# design.net
KiCad netlist of a schematic drawn in Altium Designer
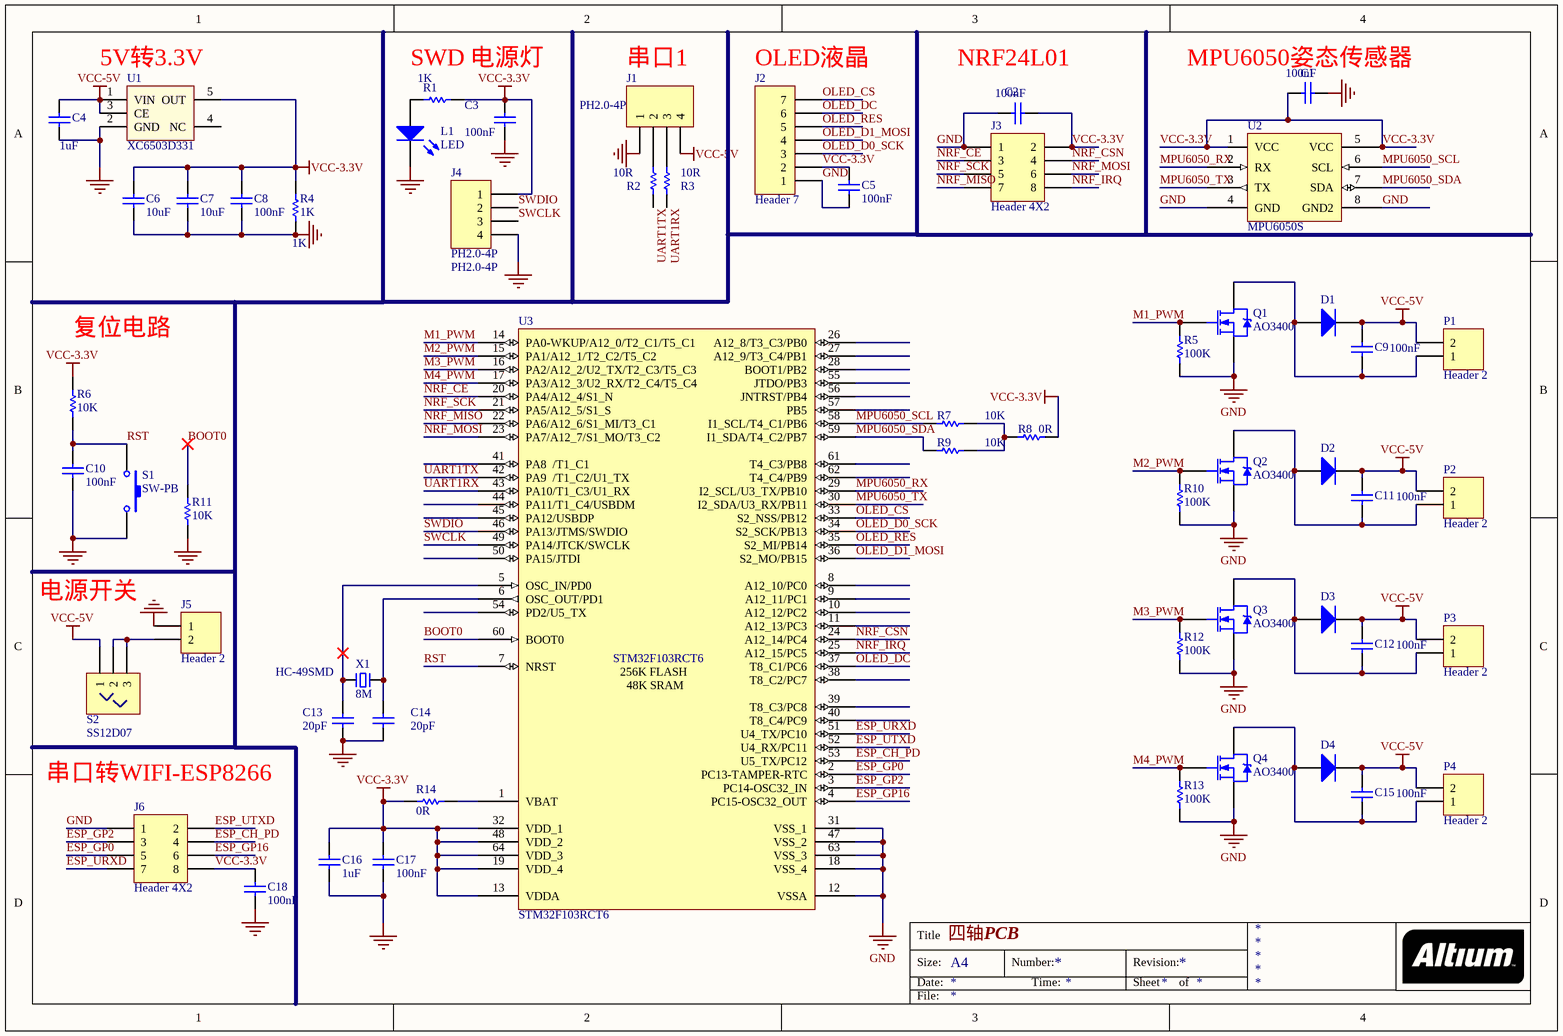
[diagram p0: 四轴.SchDoc]

(export (version "E")
  (design (tool "Eeschema 10.0.6"))
  (components
    (comp (ref "C1")
      (value "100nF")
      (footprint "LiyaoPCB库:0603")
      (description "Capacitor")
      (fields (field (name "PUBLISHER") "Altium Limited"))
      (libsource (lib "Miscellaneous Devices") (part "Cap"))
    )
    (comp (ref "C2")
      (value "100nF")
      (footprint "LiyaoPCB库:0603")
      (description "Capacitor")
      (fields (field (name "PUBLISHER") "Altium Limited"))
      (libsource (lib "Miscellaneous Devices") (part "Cap"))
    )
    (comp (ref "C3")
      (value "100nF")
      (footprint "0603")
      (description "Capacitor")
      (fields (field (name "PUBLISHER") "Altium Limited"))
      (libsource (lib "Miscellaneous Devices") (part "Cap"))
    )
    (comp (ref "C4")
      (value "1uF")
      (footprint "0603")
      (description "Capacitor")
      (fields (field (name "PUBLISHER") "Altium Limited"))
      (libsource (lib "Miscellaneous Devices") (part "Cap"))
    )
    (comp (ref "C5")
      (value "100nF")
      (footprint "LiyaoPCB库:0603")
      (description "Capacitor")
      (fields (field (name "PUBLISHER") "Altium Limited"))
      (libsource (lib "Miscellaneous Devices") (part "Cap"))
    )
    (comp (ref "C6")
      (value "10uF")
      (footprint "0603")
      (description "Capacitor")
      (fields (field (name "PUBLISHER") "Altium Limited"))
      (libsource (lib "Miscellaneous Devices") (part "Cap"))
    )
    (comp (ref "C7")
      (value "10uF")
      (footprint "0603")
      (description "Capacitor")
      (fields (field (name "PUBLISHER") "Altium Limited"))
      (libsource (lib "Miscellaneous Devices") (part "Cap"))
    )
    (comp (ref "C8")
      (value "100nF")
      (footprint "0603")
      (description "Capacitor")
      (fields (field (name "PUBLISHER") "Altium Limited"))
      (libsource (lib "Miscellaneous Devices") (part "Cap"))
    )
    (comp (ref "C9")
      (value "100nF")
      (footprint "0603")
      (description "Capacitor")
      (fields (field (name "PUBLISHER") "Altium Limited"))
      (libsource (lib "Miscellaneous Devices") (part "Cap"))
    )
    (comp (ref "C10")
      (value "100nF")
      (footprint "0603")
      (description "Capacitor")
      (fields (field (name "PUBLISHER") "Altium Limited"))
      (libsource (lib "Miscellaneous Devices") (part "Cap"))
    )
    (comp (ref "C11")
      (value "100nF")
      (footprint "0603")
      (description "Capacitor")
      (fields (field (name "PUBLISHER") "Altium Limited"))
      (libsource (lib "Miscellaneous Devices") (part "Cap"))
    )
    (comp (ref "C12")
      (value "100nF")
      (footprint "0603")
      (description "Capacitor")
      (fields (field (name "PUBLISHER") "Altium Limited"))
      (libsource (lib "Miscellaneous Devices") (part "Cap"))
    )
    (comp (ref "C13")
      (value "20pF")
      (footprint "0603")
      (description "Capacitor")
      (fields (field (name "PUBLISHER") "Altium Limited"))
      (libsource (lib "Miscellaneous Devices") (part "Cap"))
    )
    (comp (ref "C14")
      (value "20pF")
      (footprint "0603")
      (description "Capacitor")
      (fields (field (name "PUBLISHER") "Altium Limited"))
      (libsource (lib "Miscellaneous Devices") (part "Cap"))
    )
    (comp (ref "C15")
      (value "100nF")
      (footprint "0603")
      (description "Capacitor")
      (fields (field (name "PUBLISHER") "Altium Limited"))
      (libsource (lib "Miscellaneous Devices") (part "Cap"))
    )
    (comp (ref "C16")
      (value "1uF")
      (footprint "LiyaoPCB库:0603")
      (description "Capacitor")
      (fields (field (name "PUBLISHER") "Altium Limited"))
      (libsource (lib "Miscellaneous Devices") (part "Cap"))
    )
    (comp (ref "C17")
      (value "100nF")
      (footprint "LiyaoPCB库:0603")
      (description "Capacitor")
      (fields (field (name "PUBLISHER") "Altium Limited"))
      (libsource (lib "Miscellaneous Devices") (part "Cap"))
    )
    (comp (ref "C18")
      (value "100nF")
      (footprint "LiyaoPCB库:0603")
      (description "Capacitor")
      (fields (field (name "PUBLISHER") "Altium Limited"))
      (libsource (lib "Miscellaneous Devices") (part "Cap"))
    )
    (comp (ref "D1")
      (value "SS14")
      (footprint "LiyaoPCB库:SMA")
      (description "28V 1A")
      (fields (field (name "PUBLISHER") "Altium Limited"))
      (libsource (lib "Liyao原理图库") (part "SS14"))
    )
    (comp (ref "D2")
      (value "SS14")
      (footprint "LiyaoPCB库:SMA")
      (description "28V 1A")
      (fields (field (name "PUBLISHER") "Altium Limited"))
      (libsource (lib "Liyao原理图库") (part "SS14"))
    )
    (comp (ref "D3")
      (value "SS14")
      (footprint "LiyaoPCB库:SMA")
      (description "28V 1A")
      (fields (field (name "PUBLISHER") "Altium Limited"))
      (libsource (lib "Liyao原理图库") (part "SS14"))
    )
    (comp (ref "D4")
      (value "SS14")
      (footprint "LiyaoPCB库:SMA")
      (description "28V 1A")
      (fields (field (name "PUBLISHER") "Altium Limited"))
      (libsource (lib "Liyao原理图库") (part "SS14"))
    )
    (comp (ref "J1")
      (value "PH2.0-4P")
      (footprint "PH2.0-4P")
      (description "Header, 4-Pin")
      (fields (field (name "PUBLISHER") "Altium Limited"))
      (libsource (lib "Miscellaneous Connectors") (part "Header 4"))
    )
    (comp (ref "J2")
      (value "Header 7")
      (footprint "HDR1X7")
      (description "Header, 7-Pin")
      (fields (field (name "PUBLISHER") "Altium Limited"))
      (libsource (lib "Miscellaneous Connectors") (part "Header 7"))
    )
    (comp (ref "J3")
      (value "Header 4X2")
      (footprint "HDR2X4")
      (description "Header, 4-Pin, Dual row")
      (fields (field (name "PUBLISHER") "Altium Limited"))
      (libsource (lib "Miscellaneous Connectors") (part "Header 4X2"))
    )
    (comp (ref "J4")
      (value "PH2.0-4P")
      (footprint "PH2.0-4P")
      (description "Header, 4-Pin")
      (fields (field (name "ALTIUM_VALUE") "PH2.0-4P") (field (name "PUBLISHER") "Altium Limited"))
      (libsource (lib "") (part "Header 4_1"))
    )
    (comp (ref "J5")
      (value "Header 2")
      (footprint "PH2.0-2P")
      (description "Header, 2-Pin")
      (fields (field (name "PUBLISHER") "Altium Limited"))
      (libsource (lib "") (part "Header 2_1"))
    )
    (comp (ref "J6")
      (value "Header 4X2")
      (footprint "HDR2X4")
      (description "Header, 4-Pin, Dual row")
      (fields (field (name "PUBLISHER") "Altium Limited"))
      (libsource (lib "Miscellaneous Connectors") (part "Header 4X2"))
    )
    (comp (ref "L1") (value "LED") (footprint "0603") (libsource (lib "Sparks") (part "LED")))
    (comp (ref "P1")
      (value "Header 2")
      (footprint "HDR1X2")
      (description "Header, 2-Pin")
      (fields (field (name "PUBLISHER") "Altium Limited"))
      (libsource (lib "Miscellaneous Connectors") (part "Header 2"))
    )
    (comp (ref "P2")
      (value "Header 2")
      (footprint "HDR1X2")
      (description "Header, 2-Pin")
      (fields (field (name "PUBLISHER") "Altium Limited"))
      (libsource (lib "Miscellaneous Connectors") (part "Header 2"))
    )
    (comp (ref "P3")
      (value "Header 2")
      (footprint "HDR1X2")
      (description "Header, 2-Pin")
      (fields (field (name "PUBLISHER") "Altium Limited"))
      (libsource (lib "Miscellaneous Connectors") (part "Header 2"))
    )
    (comp (ref "P4")
      (value "Header 2")
      (footprint "HDR1X2")
      (description "Header, 2-Pin")
      (fields (field (name "PUBLISHER") "Altium Limited"))
      (libsource (lib "Miscellaneous Connectors") (part "Header 2"))
    )
    (comp (ref "Q1")
      (value "AO3400")
      (footprint "SOT-23")
      (description "N-Channel MOSFET")
      (fields (field (name "PUBLISHER") "Altium Limited"))
      (libsource (lib "Liyao原理图库") (part "MOS-N"))
    )
    (comp (ref "Q2")
      (value "AO3400")
      (footprint "SOT-23")
      (description "N-Channel MOSFET")
      (fields (field (name "PUBLISHER") "Altium Limited"))
      (libsource (lib "Liyao原理图库") (part "MOS-N"))
    )
    (comp (ref "Q3")
      (value "AO3400")
      (footprint "SOT-23")
      (description "N-Channel MOSFET")
      (fields (field (name "PUBLISHER") "Altium Limited"))
      (libsource (lib "Liyao原理图库") (part "MOS-N"))
    )
    (comp (ref "Q4")
      (value "AO3400")
      (footprint "SOT-23")
      (description "N-Channel MOSFET")
      (fields (field (name "PUBLISHER") "Altium Limited"))
      (libsource (lib "Liyao原理图库") (part "MOS-N"))
    )
    (comp (ref "R1")
      (value "1K")
      (footprint "0603")
      (description "Resistor")
      (fields (field (name "PUBLISHER") "Altium Limited"))
      (libsource (lib "Miscellaneous Devices") (part "Res1"))
    )
    (comp (ref "R2")
      (value "10R")
      (footprint "0603")
      (description "Resistor")
      (fields (field (name "PUBLISHER") "Altium Limited"))
      (libsource (lib "Miscellaneous Devices") (part "Res1"))
    )
    (comp (ref "R3")
      (value "10R")
      (footprint "0603")
      (description "Resistor")
      (fields (field (name "PUBLISHER") "Altium Limited"))
      (libsource (lib "Miscellaneous Devices") (part "Res1"))
    )
    (comp (ref "R4")
      (value "1K")
      (footprint "0603")
      (description "Resistor")
      (fields (field (name "ALTIUM_VALUE") "1K") (field (name "PUBLISHER") "Altium Limited"))
      (libsource (lib "Miscellaneous Devices") (part "Res1"))
    )
    (comp (ref "R5")
      (value "100K")
      (footprint "LiyaoPCB库:0603")
      (description "Resistor")
      (fields (field (name "PUBLISHER") "Altium Limited"))
      (libsource (lib "Miscellaneous Devices") (part "Res1"))
    )
    (comp (ref "R6")
      (value "10K")
      (footprint "0603")
      (description "Resistor")
      (fields (field (name "PUBLISHER") "Altium Limited"))
      (libsource (lib "Miscellaneous Devices") (part "Res1"))
    )
    (comp (ref "R7")
      (value "10K")
      (footprint "0603")
      (description "Resistor")
      (fields (field (name "PUBLISHER") "Altium Limited"))
      (libsource (lib "Miscellaneous Devices") (part "Res1"))
    )
    (comp (ref "R8")
      (value "0R")
      (footprint "0603")
      (description "Resistor")
      (fields (field (name "PUBLISHER") "Altium Limited"))
      (libsource (lib "Miscellaneous Devices") (part "Res1"))
    )
    (comp (ref "R9")
      (value "10K")
      (footprint "0603")
      (description "Resistor")
      (fields (field (name "PUBLISHER") "Altium Limited"))
      (libsource (lib "Miscellaneous Devices") (part "Res1"))
    )
    (comp (ref "R10")
      (value "100K")
      (footprint "LiyaoPCB库:0603")
      (description "Resistor")
      (fields (field (name "PUBLISHER") "Altium Limited"))
      (libsource (lib "Miscellaneous Devices") (part "Res1"))
    )
    (comp (ref "R11")
      (value "10K")
      (footprint "0603")
      (description "Resistor")
      (fields (field (name "PUBLISHER") "Altium Limited"))
      (libsource (lib "Miscellaneous Devices") (part "Res1"))
    )
    (comp (ref "R12")
      (value "100K")
      (footprint "LiyaoPCB库:0603")
      (description "Resistor")
      (fields (field (name "PUBLISHER") "Altium Limited"))
      (libsource (lib "Miscellaneous Devices") (part "Res1"))
    )
    (comp (ref "R13")
      (value "100K")
      (footprint "LiyaoPCB库:0603")
      (description "Resistor")
      (fields (field (name "PUBLISHER") "Altium Limited"))
      (libsource (lib "Miscellaneous Devices") (part "Res1"))
    )
    (comp (ref "R14")
      (value "0R")
      (footprint "0603")
      (description "Resistor")
      (fields (field (name "PUBLISHER") "Altium Limited"))
      (libsource (lib "Miscellaneous Devices") (part "Res1"))
    )
    (comp (ref "S1")
      (value "SW-PB")
      (footprint "SW-KEY")
      (description "Switch")
      (fields (field (name "PUBLISHER") "Altium Limited"))
      (libsource (lib "Miscellaneous Devices") (part "SW-PB"))
    )
    (comp (ref "S2")
      (value "SS12D07")
      (footprint "LiyaoPCB库:SS-12D07")
      (libsource (lib "Liyao原理图库") (part "SS12D07"))
    )
    (comp (ref "U1")
      (value "XC6503D331")
      (footprint "SOT23-5")
      (libsource (lib "CYSchlib") (part "XC6503Dxxx"))
    )
    (comp (ref "U2")
      (value "MPU6050S")
      (footprint "LiyaoPCB库:MPU6050S")
      (libsource (lib "Liyao原理图库") (part "MPU6050S"))
    )
    (comp (ref "U3")
      (value "STM32F103RCT6")
      (footprint "LQFP64_N")
      (description "256K Flash 48K RAM")
      (fields (field (name "PUBLISHER") "Altium Limited"))
      (libsource (lib "Liyao原理图库") (part "STM32F103RCT6"))
    )
    (comp (ref "X1")
      (value "8M")
      (footprint "HC-49SMD")
      (fields (field (name "ALTIUM_VALUE") "HC-49SMD"))
      (libsource (lib "CYSchlib") (part "XTAL"))
    )
  )
  (nets
    (net (code "1") (name "/BOOT0") (class "Default")
      (node (ref "R11") (pin "1") (pinfunction "1_1") (pintype "passive"))
      (node (ref "U3") (pin "60") (pinfunction "BOOT0_60") (pintype "input"))
    )
    (net (code "2") (name "/ESP_CH_PD") (class "Default")
      (node (ref "J6") (pin "4") (pinfunction "4_4") (pintype "passive"))
      (node (ref "U3") (pin "53") (pinfunction "U5_TX/PC12_53") (pintype "bidirectional"))
    )
    (net (code "3") (name "/ESP_GP0") (class "Default")
      (node (ref "J6") (pin "5") (pinfunction "5_5") (pintype "passive"))
      (node (ref "U3") (pin "2") (pinfunction "PC13-TAMPER-RTC_2") (pintype "bidirectional"))
    )
    (net (code "4") (name "/ESP_GP2") (class "Default")
      (node (ref "J6") (pin "3") (pinfunction "3_3") (pintype "passive"))
      (node (ref "U3") (pin "3") (pinfunction "PC14-OSC32_IN_3") (pintype "bidirectional"))
    )
    (net (code "5") (name "/ESP_GP16") (class "Default")
      (node (ref "J6") (pin "6") (pinfunction "6_6") (pintype "passive"))
      (node (ref "U3") (pin "4") (pinfunction "PC15-OSC32_OUT_4") (pintype "bidirectional"))
    )
    (net (code "6") (name "/ESP_URXD") (class "Default")
      (node (ref "J6") (pin "7") (pinfunction "7_7") (pintype "passive"))
      (node (ref "U3") (pin "51") (pinfunction "U4_TX/PC10_51") (pintype "bidirectional"))
    )
    (net (code "7") (name "/ESP_UTXD") (class "Default")
      (node (ref "J6") (pin "2") (pinfunction "2_2") (pintype "passive"))
      (node (ref "U3") (pin "52") (pinfunction "U4_RX/PC11_52") (pintype "bidirectional"))
    )
    (net (code "8") (name "/M1_PWM") (class "Default")
      (node (ref "Q1") (pin "1") (pinfunction "G_1") (pintype "passive"))
      (node (ref "R5") (pin "2") (pinfunction "2_2") (pintype "passive"))
      (node (ref "U3") (pin "14") (pinfunction "PA0-WKUP/A12_0/T2_C1/T5_C1_14") (pintype "bidirectional"))
    )
    (net (code "9") (name "/M2_PWM") (class "Default")
      (node (ref "Q2") (pin "1") (pinfunction "G_1") (pintype "passive"))
      (node (ref "R10") (pin "2") (pinfunction "2_2") (pintype "passive"))
      (node (ref "U3") (pin "15") (pinfunction "PA1/A12_1/T2_C2/T5_C2_15") (pintype "bidirectional"))
    )
    (net (code "10") (name "/M3_PWM") (class "Default")
      (node (ref "Q3") (pin "1") (pinfunction "G_1") (pintype "passive"))
      (node (ref "R12") (pin "2") (pinfunction "2_2") (pintype "passive"))
      (node (ref "U3") (pin "16") (pinfunction "PA2/A12_2/U2_TX/T2_C3/T5_C3_16") (pintype "bidirectional"))
    )
    (net (code "11") (name "/M4_PWM") (class "Default")
      (node (ref "Q4") (pin "1") (pinfunction "G_1") (pintype "passive"))
      (node (ref "R13") (pin "2") (pinfunction "2_2") (pintype "passive"))
      (node (ref "U3") (pin "17") (pinfunction "PA3/A12_3/U2_RX/T2_C4/T5_C4_17") (pintype "bidirectional"))
    )
    (net (code "12") (name "/MPU6050_RX") (class "Default")
      (node (ref "U2") (pin "2") (pinfunction "RX_2") (pintype "input"))
      (node (ref "U3") (pin "29") (pinfunction "I2_SCL/U3_TX/PB10_29") (pintype "bidirectional"))
    )
    (net (code "13") (name "/MPU6050_SCL") (class "Default")
      (node (ref "R7") (pin "1") (pinfunction "1_1") (pintype "passive"))
      (node (ref "U2") (pin "6") (pinfunction "SCL_6") (pintype "input"))
      (node (ref "U3") (pin "58") (pinfunction "I1_SCL/T4_C1/PB6_58") (pintype "bidirectional"))
    )
    (net (code "14") (name "/MPU6050_SDA") (class "Default")
      (node (ref "R9") (pin "1") (pinfunction "1_1") (pintype "passive"))
      (node (ref "U2") (pin "7") (pinfunction "SDA_7") (pintype "bidirectional"))
      (node (ref "U3") (pin "59") (pinfunction "I1_SDA/T4_C2/PB7_59") (pintype "bidirectional"))
    )
    (net (code "15") (name "/MPU6050_TX") (class "Default")
      (node (ref "U2") (pin "3") (pinfunction "TX_3") (pintype "output"))
      (node (ref "U3") (pin "30") (pinfunction "I2_SDA/U3_RX/PB11_30") (pintype "bidirectional"))
    )
    (net (code "16") (name "/NRF_CE") (class "Default")
      (node (ref "J3") (pin "3") (pinfunction "3_3") (pintype "passive"))
      (node (ref "U3") (pin "20") (pinfunction "PA4/A12_4/S1_N_20") (pintype "bidirectional"))
    )
    (net (code "17") (name "/NRF_CSN") (class "Default")
      (node (ref "J3") (pin "4") (pinfunction "4_4") (pintype "passive"))
      (node (ref "U3") (pin "24") (pinfunction "A12_14/PC4_24") (pintype "bidirectional"))
    )
    (net (code "18") (name "/NRF_IRQ") (class "Default")
      (node (ref "J3") (pin "8") (pinfunction "8_8") (pintype "passive"))
      (node (ref "U3") (pin "25") (pinfunction "A12_15/PC5_25") (pintype "bidirectional"))
    )
    (net (code "19") (name "/NRF_MISO") (class "Default")
      (node (ref "J3") (pin "7") (pinfunction "7_7") (pintype "passive"))
      (node (ref "U3") (pin "22") (pinfunction "PA6/A12_6/S1_MI/T3_C1_22") (pintype "bidirectional"))
    )
    (net (code "20") (name "/NRF_MOSI") (class "Default")
      (node (ref "J3") (pin "6") (pinfunction "6_6") (pintype "passive"))
      (node (ref "U3") (pin "23") (pinfunction "PA7/A12_7/S1_MO/T3_C2_23") (pintype "bidirectional"))
    )
    (net (code "21") (name "/NRF_SCK") (class "Default")
      (node (ref "J3") (pin "5") (pinfunction "5_5") (pintype "passive"))
      (node (ref "U3") (pin "21") (pinfunction "PA5/A12_5/S1_S_21") (pintype "bidirectional"))
    )
    (net (code "22") (name "/OLED_CS") (class "Default")
      (node (ref "J2") (pin "7") (pinfunction "7_7") (pintype "passive"))
      (node (ref "U3") (pin "33") (pinfunction "S2_NSS/PB12_33") (pintype "bidirectional"))
    )
    (net (code "23") (name "/OLED_D0_SCK") (class "Default")
      (node (ref "J2") (pin "3") (pinfunction "3_3") (pintype "passive"))
      (node (ref "U3") (pin "34") (pinfunction "S2_SCK/PB13_34") (pintype "bidirectional"))
    )
    (net (code "24") (name "/OLED_D1_MOSI") (class "Default")
      (node (ref "J2") (pin "4") (pinfunction "4_4") (pintype "passive"))
      (node (ref "U3") (pin "36") (pinfunction "S2_MO/PB15_36") (pintype "bidirectional"))
    )
    (net (code "25") (name "/OLED_DC") (class "Default")
      (node (ref "J2") (pin "6") (pinfunction "6_6") (pintype "passive"))
      (node (ref "U3") (pin "37") (pinfunction "T8_C1/PC6_37") (pintype "bidirectional"))
    )
    (net (code "26") (name "/OLED_RES") (class "Default")
      (node (ref "J2") (pin "5") (pinfunction "5_5") (pintype "passive"))
      (node (ref "U3") (pin "35") (pinfunction "S2_MI/PB14_35") (pintype "bidirectional"))
    )
    (net (code "27") (name "/RST") (class "Default")
      (node (ref "C10") (pin "1") (pinfunction "1_1") (pintype "passive"))
      (node (ref "R6") (pin "2") (pinfunction "2_2") (pintype "passive"))
      (node (ref "S1") (pin "1") (pinfunction "1_1") (pintype "passive"))
      (node (ref "U3") (pin "7") (pinfunction "NRST_7") (pintype "bidirectional"))
    )
    (net (code "28") (name "/SWCLK") (class "Default")
      (node (ref "J4") (pin "3") (pinfunction "3_3") (pintype "passive"))
      (node (ref "U3") (pin "49") (pinfunction "PA14/JTCK/SWCLK_49") (pintype "bidirectional"))
    )
    (net (code "29") (name "/SWDIO") (class "Default")
      (node (ref "J4") (pin "2") (pinfunction "2_2") (pintype "passive"))
      (node (ref "U3") (pin "46") (pinfunction "PA13/JTMS/SWDIO_46") (pintype "bidirectional"))
    )
    (net (code "30") (name "/UART1RX") (class "Default")
      (node (ref "R3") (pin "2") (pinfunction "2_2") (pintype "passive"))
      (node (ref "U3") (pin "43") (pinfunction "PA10/T1_C3/U1_RX_43") (pintype "bidirectional"))
    )
    (net (code "31") (name "/UART1TX") (class "Default")
      (node (ref "R2") (pin "2") (pinfunction "2_2") (pintype "passive"))
      (node (ref "U3") (pin "42") (pinfunction "PA9__/T1_C2/U1_TX_42") (pintype "bidirectional"))
    )
    (net (code "32") (name "GND") (class "Default")
      (node (ref "C1") (pin "2") (pinfunction "2_2") (pintype "passive"))
      (node (ref "C10") (pin "2") (pinfunction "2_2") (pintype "passive"))
      (node (ref "C13") (pin "1") (pinfunction "1_1") (pintype "passive"))
      (node (ref "C14") (pin "1") (pinfunction "1_1") (pintype "passive"))
      (node (ref "C16") (pin "1") (pinfunction "1_1") (pintype "passive"))
      (node (ref "C17") (pin "1") (pinfunction "1_1") (pintype "passive"))
      (node (ref "C18") (pin "2") (pinfunction "2_2") (pintype "passive"))
      (node (ref "C2") (pin "2") (pinfunction "2_2") (pintype "passive"))
      (node (ref "C3") (pin "2") (pinfunction "2_2") (pintype "passive"))
      (node (ref "C4") (pin "1") (pinfunction "1_1") (pintype "passive"))
      (node (ref "C5") (pin "2") (pinfunction "2_2") (pintype "passive"))
      (node (ref "C6") (pin "2") (pinfunction "2_2") (pintype "passive"))
      (node (ref "C7") (pin "1") (pinfunction "1_1") (pintype "passive"))
      (node (ref "C8") (pin "1") (pinfunction "1_1") (pintype "passive"))
      (node (ref "J1") (pin "1") (pinfunction "1_1") (pintype "passive"))
      (node (ref "J2") (pin "1") (pinfunction "1_1") (pintype "passive"))
      (node (ref "J3") (pin "1") (pinfunction "1_1") (pintype "passive"))
      (node (ref "J4") (pin "4") (pinfunction "4_4") (pintype "passive"))
      (node (ref "J5") (pin "1") (pinfunction "1_1") (pintype "passive"))
      (node (ref "J6") (pin "1") (pinfunction "1_1") (pintype "passive"))
      (node (ref "L1") (pin "2") (pinfunction "K_2") (pintype "passive"))
      (node (ref "Q1") (pin "2") (pinfunction "S_2") (pintype "passive"))
      (node (ref "Q2") (pin "2") (pinfunction "S_2") (pintype "passive"))
      (node (ref "Q3") (pin "2") (pinfunction "S_2") (pintype "passive"))
      (node (ref "Q4") (pin "2") (pinfunction "S_2") (pintype "passive"))
      (node (ref "R10") (pin "1") (pinfunction "1_1") (pintype "passive"))
      (node (ref "R11") (pin "2") (pinfunction "2_2") (pintype "passive"))
      (node (ref "R12") (pin "1") (pinfunction "1_1") (pintype "passive"))
      (node (ref "R13") (pin "1") (pinfunction "1_1") (pintype "passive"))
      (node (ref "R4") (pin "1") (pinfunction "1_1") (pintype "passive"))
      (node (ref "R5") (pin "1") (pinfunction "1_1") (pintype "passive"))
      (node (ref "S1") (pin "2") (pinfunction "2_2") (pintype "passive"))
      (node (ref "U1") (pin "2") (pinfunction "GND_2") (pintype "passive"))
      (node (ref "U2") (pin "4") (pinfunction "GND_4") (pintype "power_in"))
      (node (ref "U2") (pin "8") (pinfunction "GND2_8") (pintype "passive"))
      (node (ref "U3") (pin "12") (pinfunction "VSSA_12") (pintype "power_in"))
      (node (ref "U3") (pin "18") (pinfunction "VSS_4_18") (pintype "power_in"))
      (node (ref "U3") (pin "31") (pinfunction "VSS_1_31") (pintype "power_in"))
      (node (ref "U3") (pin "47") (pinfunction "VSS_2_47") (pintype "power_in"))
      (node (ref "U3") (pin "63") (pinfunction "VSS_3_63") (pintype "power_in"))
    )
    (net (code "33") (name "Net-(D1-A)") (class "Default")
      (node (ref "C9") (pin "1") (pinfunction "1_1") (pintype "passive"))
      (node (ref "D1") (pin "1") (pinfunction "A_1") (pintype "passive"))
      (node (ref "P1") (pin "1") (pinfunction "1_1") (pintype "passive"))
      (node (ref "Q1") (pin "3") (pinfunction "D_3") (pintype "passive"))
    )
    (net (code "34") (name "Net-(D2-A)") (class "Default")
      (node (ref "C11") (pin "1") (pinfunction "1_1") (pintype "passive"))
      (node (ref "D2") (pin "1") (pinfunction "A_1") (pintype "passive"))
      (node (ref "P2") (pin "1") (pinfunction "1_1") (pintype "passive"))
      (node (ref "Q2") (pin "3") (pinfunction "D_3") (pintype "passive"))
    )
    (net (code "35") (name "Net-(D3-A)") (class "Default")
      (node (ref "C12") (pin "1") (pinfunction "1_1") (pintype "passive"))
      (node (ref "D3") (pin "1") (pinfunction "A_1") (pintype "passive"))
      (node (ref "P3") (pin "1") (pinfunction "1_1") (pintype "passive"))
      (node (ref "Q3") (pin "3") (pinfunction "D_3") (pintype "passive"))
    )
    (net (code "36") (name "Net-(D4-A)") (class "Default")
      (node (ref "C15") (pin "1") (pinfunction "1_1") (pintype "passive"))
      (node (ref "D4") (pin "1") (pinfunction "A_1") (pintype "passive"))
      (node (ref "P4") (pin "1") (pinfunction "1_1") (pintype "passive"))
      (node (ref "Q4") (pin "3") (pinfunction "D_3") (pintype "passive"))
    )
    (net (code "37") (name "Net-(J1-Pad2)") (class "Default")
      (node (ref "J1") (pin "2") (pinfunction "2_2") (pintype "passive"))
      (node (ref "R2") (pin "1") (pinfunction "1_1") (pintype "passive"))
    )
    (net (code "38") (name "Net-(J1-Pad3)") (class "Default")
      (node (ref "J1") (pin "3") (pinfunction "3_3") (pintype "passive"))
      (node (ref "R3") (pin "1") (pinfunction "1_1") (pintype "passive"))
    )
    (net (code "39") (name "Net-(J5-Pad2)") (class "Default")
      (node (ref "J5") (pin "2") (pinfunction "2_2") (pintype "passive"))
      (node (ref "S2") (pin "2") (pinfunction "2_2") (pintype "passive"))
      (node (ref "S2") (pin "3") (pinfunction "3_3") (pintype "passive"))
    )
    (net (code "40") (name "Net-(L1-A)") (class "Default")
      (node (ref "L1") (pin "1") (pinfunction "A_1") (pintype "passive"))
      (node (ref "R1") (pin "1") (pinfunction "1_1") (pintype "passive"))
    )
    (net (code "41") (name "Net-(R7-Pad2)") (class "Default")
      (node (ref "R7") (pin "2") (pinfunction "2_2") (pintype "passive"))
      (node (ref "R8") (pin "2") (pinfunction "2_2") (pintype "passive"))
      (node (ref "R9") (pin "2") (pinfunction "2_2") (pintype "passive"))
    )
    (net (code "42") (name "Net-(U3-OSC_IN{slash}PD0)") (class "Default")
      (node (ref "C13") (pin "2") (pinfunction "2_2") (pintype "passive"))
      (node (ref "U3") (pin "5") (pinfunction "OSC_IN/PD0_5") (pintype "input"))
      (node (ref "X1") (pin "2") (pinfunction "2_2") (pintype "passive"))
    )
    (net (code "43") (name "Net-(U3-OSC_OUT{slash}PD1)") (class "Default")
      (node (ref "C14") (pin "2") (pinfunction "2_2") (pintype "passive"))
      (node (ref "U3") (pin "6") (pinfunction "OSC_OUT/PD1_6") (pintype "output"))
      (node (ref "X1") (pin "1") (pinfunction "1_1") (pintype "passive"))
    )
    (net (code "44") (name "Net-(U3-VBAT)") (class "Default")
      (node (ref "R14") (pin "2") (pinfunction "2_2") (pintype "passive"))
      (node (ref "U3") (pin "1") (pinfunction "VBAT_1") (pintype "power_in"))
    )
    (net (code "45") (name "VCC-3.3V") (class "Default")
      (node (ref "C1") (pin "1") (pinfunction "1_1") (pintype "passive"))
      (node (ref "C16") (pin "2") (pinfunction "2_2") (pintype "passive"))
      (node (ref "C17") (pin "2") (pinfunction "2_2") (pintype "passive"))
      (node (ref "C18") (pin "1") (pinfunction "1_1") (pintype "passive"))
      (node (ref "C2") (pin "1") (pinfunction "1_1") (pintype "passive"))
      (node (ref "C3") (pin "1") (pinfunction "1_1") (pintype "passive"))
      (node (ref "C5") (pin "1") (pinfunction "1_1") (pintype "passive"))
      (node (ref "C6") (pin "1") (pinfunction "1_1") (pintype "passive"))
      (node (ref "C7") (pin "2") (pinfunction "2_2") (pintype "passive"))
      (node (ref "C8") (pin "2") (pinfunction "2_2") (pintype "passive"))
      (node (ref "J2") (pin "2") (pinfunction "2_2") (pintype "passive"))
      (node (ref "J3") (pin "2") (pinfunction "2_2") (pintype "passive"))
      (node (ref "J4") (pin "1") (pinfunction "1_1") (pintype "passive"))
      (node (ref "J6") (pin "8") (pinfunction "8_8") (pintype "passive"))
      (node (ref "R1") (pin "2") (pinfunction "2_2") (pintype "passive"))
      (node (ref "R14") (pin "1") (pinfunction "1_1") (pintype "passive"))
      (node (ref "R4") (pin "2") (pinfunction "2_2") (pintype "passive"))
      (node (ref "R6") (pin "1") (pinfunction "1_1") (pintype "passive"))
      (node (ref "R8") (pin "1") (pinfunction "1_1") (pintype "passive"))
      (node (ref "U1") (pin "5") (pinfunction "OUT_5") (pintype "passive"))
      (node (ref "U2") (pin "1") (pinfunction "VCC_1") (pintype "power_in"))
      (node (ref "U2") (pin "5") (pinfunction "VCC_5") (pintype "power_in"))
      (node (ref "U3") (pin "13") (pinfunction "VDDA_13") (pintype "power_in"))
      (node (ref "U3") (pin "19") (pinfunction "VDD_4_19") (pintype "power_in"))
      (node (ref "U3") (pin "32") (pinfunction "VDD_1_32") (pintype "power_in"))
      (node (ref "U3") (pin "48") (pinfunction "VDD_2_48") (pintype "power_in"))
      (node (ref "U3") (pin "64") (pinfunction "VDD_3_64") (pintype "power_in"))
    )
    (net (code "46") (name "VCC-5V") (class "Default")
      (node (ref "C11") (pin "2") (pinfunction "2_2") (pintype "passive"))
      (node (ref "C12") (pin "2") (pinfunction "2_2") (pintype "passive"))
      (node (ref "C15") (pin "2") (pinfunction "2_2") (pintype "passive"))
      (node (ref "C4") (pin "2") (pinfunction "2_2") (pintype "passive"))
      (node (ref "C9") (pin "2") (pinfunction "2_2") (pintype "passive"))
      (node (ref "D1") (pin "2") (pinfunction "K_2") (pintype "passive"))
      (node (ref "D2") (pin "2") (pinfunction "K_2") (pintype "passive"))
      (node (ref "D3") (pin "2") (pinfunction "K_2") (pintype "passive"))
      (node (ref "D4") (pin "2") (pinfunction "K_2") (pintype "passive"))
      (node (ref "J1") (pin "4") (pinfunction "4_4") (pintype "passive"))
      (node (ref "P1") (pin "2") (pinfunction "2_2") (pintype "passive"))
      (node (ref "P2") (pin "2") (pinfunction "2_2") (pintype "passive"))
      (node (ref "P3") (pin "2") (pinfunction "2_2") (pintype "passive"))
      (node (ref "P4") (pin "2") (pinfunction "2_2") (pintype "passive"))
      (node (ref "S2") (pin "1") (pinfunction "1_1") (pintype "passive"))
      (node (ref "U1") (pin "1") (pinfunction "VIN_1") (pintype "passive"))
      (node (ref "U1") (pin "3") (pinfunction "CE_3") (pintype "passive"))
    )
    (net (code "47") (name "unconnected-(U1-NC-Pad4)") (class "Default")
      (node (ref "U1") (pin "4") (pinfunction "NC_4") (pintype "passive"))
    )
    (net (code "48") (name "unconnected-(U3-A12_8{slash}T3_C3{slash}PB0-Pad26)") (class "Default")
      (node (ref "U3") (pin "26") (pinfunction "A12_8/T3_C3/PB0_26") (pintype "bidirectional"))
    )
    (net (code "49") (name "unconnected-(U3-A12_9{slash}T3_C4{slash}PB1-Pad27)") (class "Default")
      (node (ref "U3") (pin "27") (pinfunction "A12_9/T3_C4/PB1_27") (pintype "bidirectional"))
    )
    (net (code "50") (name "unconnected-(U3-A12_10{slash}PC0-Pad8)") (class "Default")
      (node (ref "U3") (pin "8") (pinfunction "A12_10/PC0_8") (pintype "bidirectional"))
    )
    (net (code "51") (name "unconnected-(U3-A12_11{slash}PC1-Pad9)") (class "Default")
      (node (ref "U3") (pin "9") (pinfunction "A12_11/PC1_9") (pintype "bidirectional"))
    )
    (net (code "52") (name "unconnected-(U3-A12_12{slash}PC2-Pad10)") (class "Default")
      (node (ref "U3") (pin "10") (pinfunction "A12_12/PC2_10") (pintype "bidirectional"))
    )
    (net (code "53") (name "unconnected-(U3-A12_13{slash}PC3-Pad11)") (class "Default")
      (node (ref "U3") (pin "11") (pinfunction "A12_13/PC3_11") (pintype "bidirectional"))
    )
    (net (code "54") (name "unconnected-(U3-BOOT1{slash}PB2-Pad28)") (class "Default")
      (node (ref "U3") (pin "28") (pinfunction "BOOT1/PB2_28") (pintype "bidirectional"))
    )
    (net (code "55") (name "unconnected-(U3-JNTRST{slash}PB4-Pad56)") (class "Default")
      (node (ref "U3") (pin "56") (pinfunction "JNTRST/PB4_56") (pintype "bidirectional"))
    )
    (net (code "56") (name "unconnected-(U3-JTDO{slash}PB3-Pad55)") (class "Default")
      (node (ref "U3") (pin "55") (pinfunction "JTDO/PB3_55") (pintype "bidirectional"))
    )
    (net (code "57") (name "unconnected-(U3-PA8__{slash}T1_C1-Pad41)") (class "Default")
      (node (ref "U3") (pin "41") (pinfunction "PA8__/T1_C1_41") (pintype "bidirectional"))
    )
    (net (code "58") (name "unconnected-(U3-PA11{slash}T1_C4{slash}USBDM-Pad44)") (class "Default")
      (node (ref "U3") (pin "44") (pinfunction "PA11/T1_C4/USBDM_44") (pintype "bidirectional"))
    )
    (net (code "59") (name "unconnected-(U3-PA12{slash}USBDP-Pad45)") (class "Default")
      (node (ref "U3") (pin "45") (pinfunction "PA12/USBDP_45") (pintype "bidirectional"))
    )
    (net (code "60") (name "unconnected-(U3-PA15{slash}JTDI-Pad50)") (class "Default")
      (node (ref "U3") (pin "50") (pinfunction "PA15/JTDI_50") (pintype "bidirectional"))
    )
    (net (code "61") (name "unconnected-(U3-PB5-Pad57)") (class "Default")
      (node (ref "U3") (pin "57") (pinfunction "PB5_57") (pintype "bidirectional"))
    )
    (net (code "62") (name "unconnected-(U3-PD2{slash}U5_TX-Pad54)") (class "Default")
      (node (ref "U3") (pin "54") (pinfunction "PD2/U5_TX_54") (pintype "bidirectional"))
    )
    (net (code "63") (name "unconnected-(U3-T4_C3{slash}PB8-Pad61)") (class "Default")
      (node (ref "U3") (pin "61") (pinfunction "T4_C3/PB8_61") (pintype "bidirectional"))
    )
    (net (code "64") (name "unconnected-(U3-T4_C4{slash}PB9-Pad62)") (class "Default")
      (node (ref "U3") (pin "62") (pinfunction "T4_C4/PB9_62") (pintype "bidirectional"))
    )
    (net (code "65") (name "unconnected-(U3-T8_C2{slash}PC7-Pad38)") (class "Default")
      (node (ref "U3") (pin "38") (pinfunction "T8_C2/PC7_38") (pintype "bidirectional"))
    )
    (net (code "66") (name "unconnected-(U3-T8_C3{slash}PC8-Pad39)") (class "Default")
      (node (ref "U3") (pin "39") (pinfunction "T8_C3/PC8_39") (pintype "bidirectional"))
    )
    (net (code "67") (name "unconnected-(U3-T8_C4{slash}PC9-Pad40)") (class "Default")
      (node (ref "U3") (pin "40") (pinfunction "T8_C4/PC9_40") (pintype "bidirectional"))
    )
  )
)
